# noisy.net
KiCad netlist of a schematic drawn in EAGLE
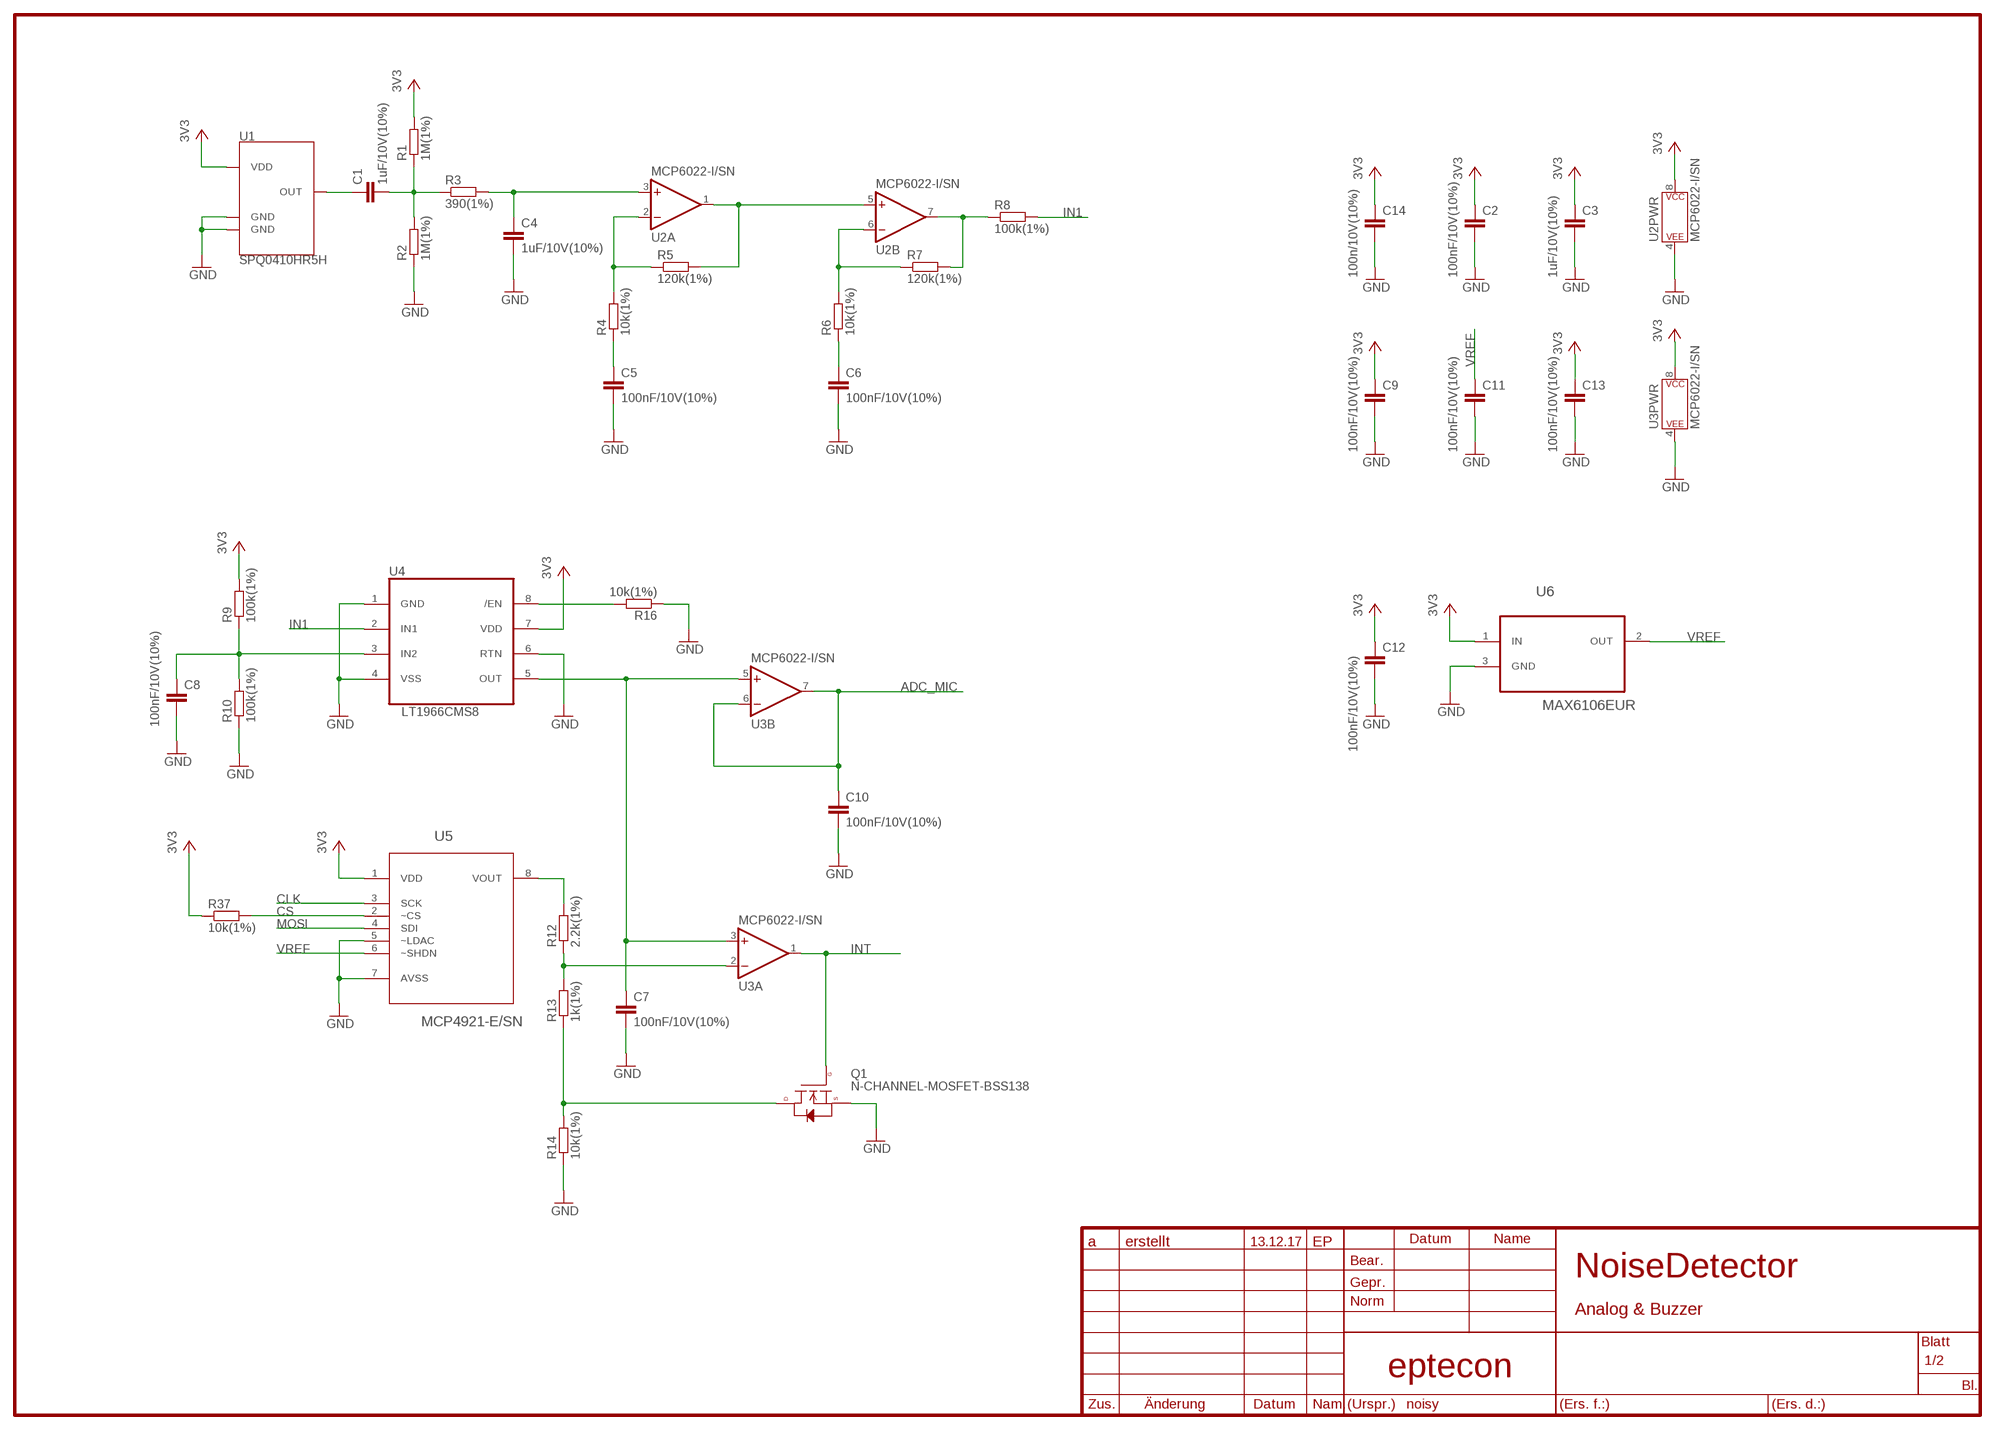
[diagram p0: schematic, sheet 1]
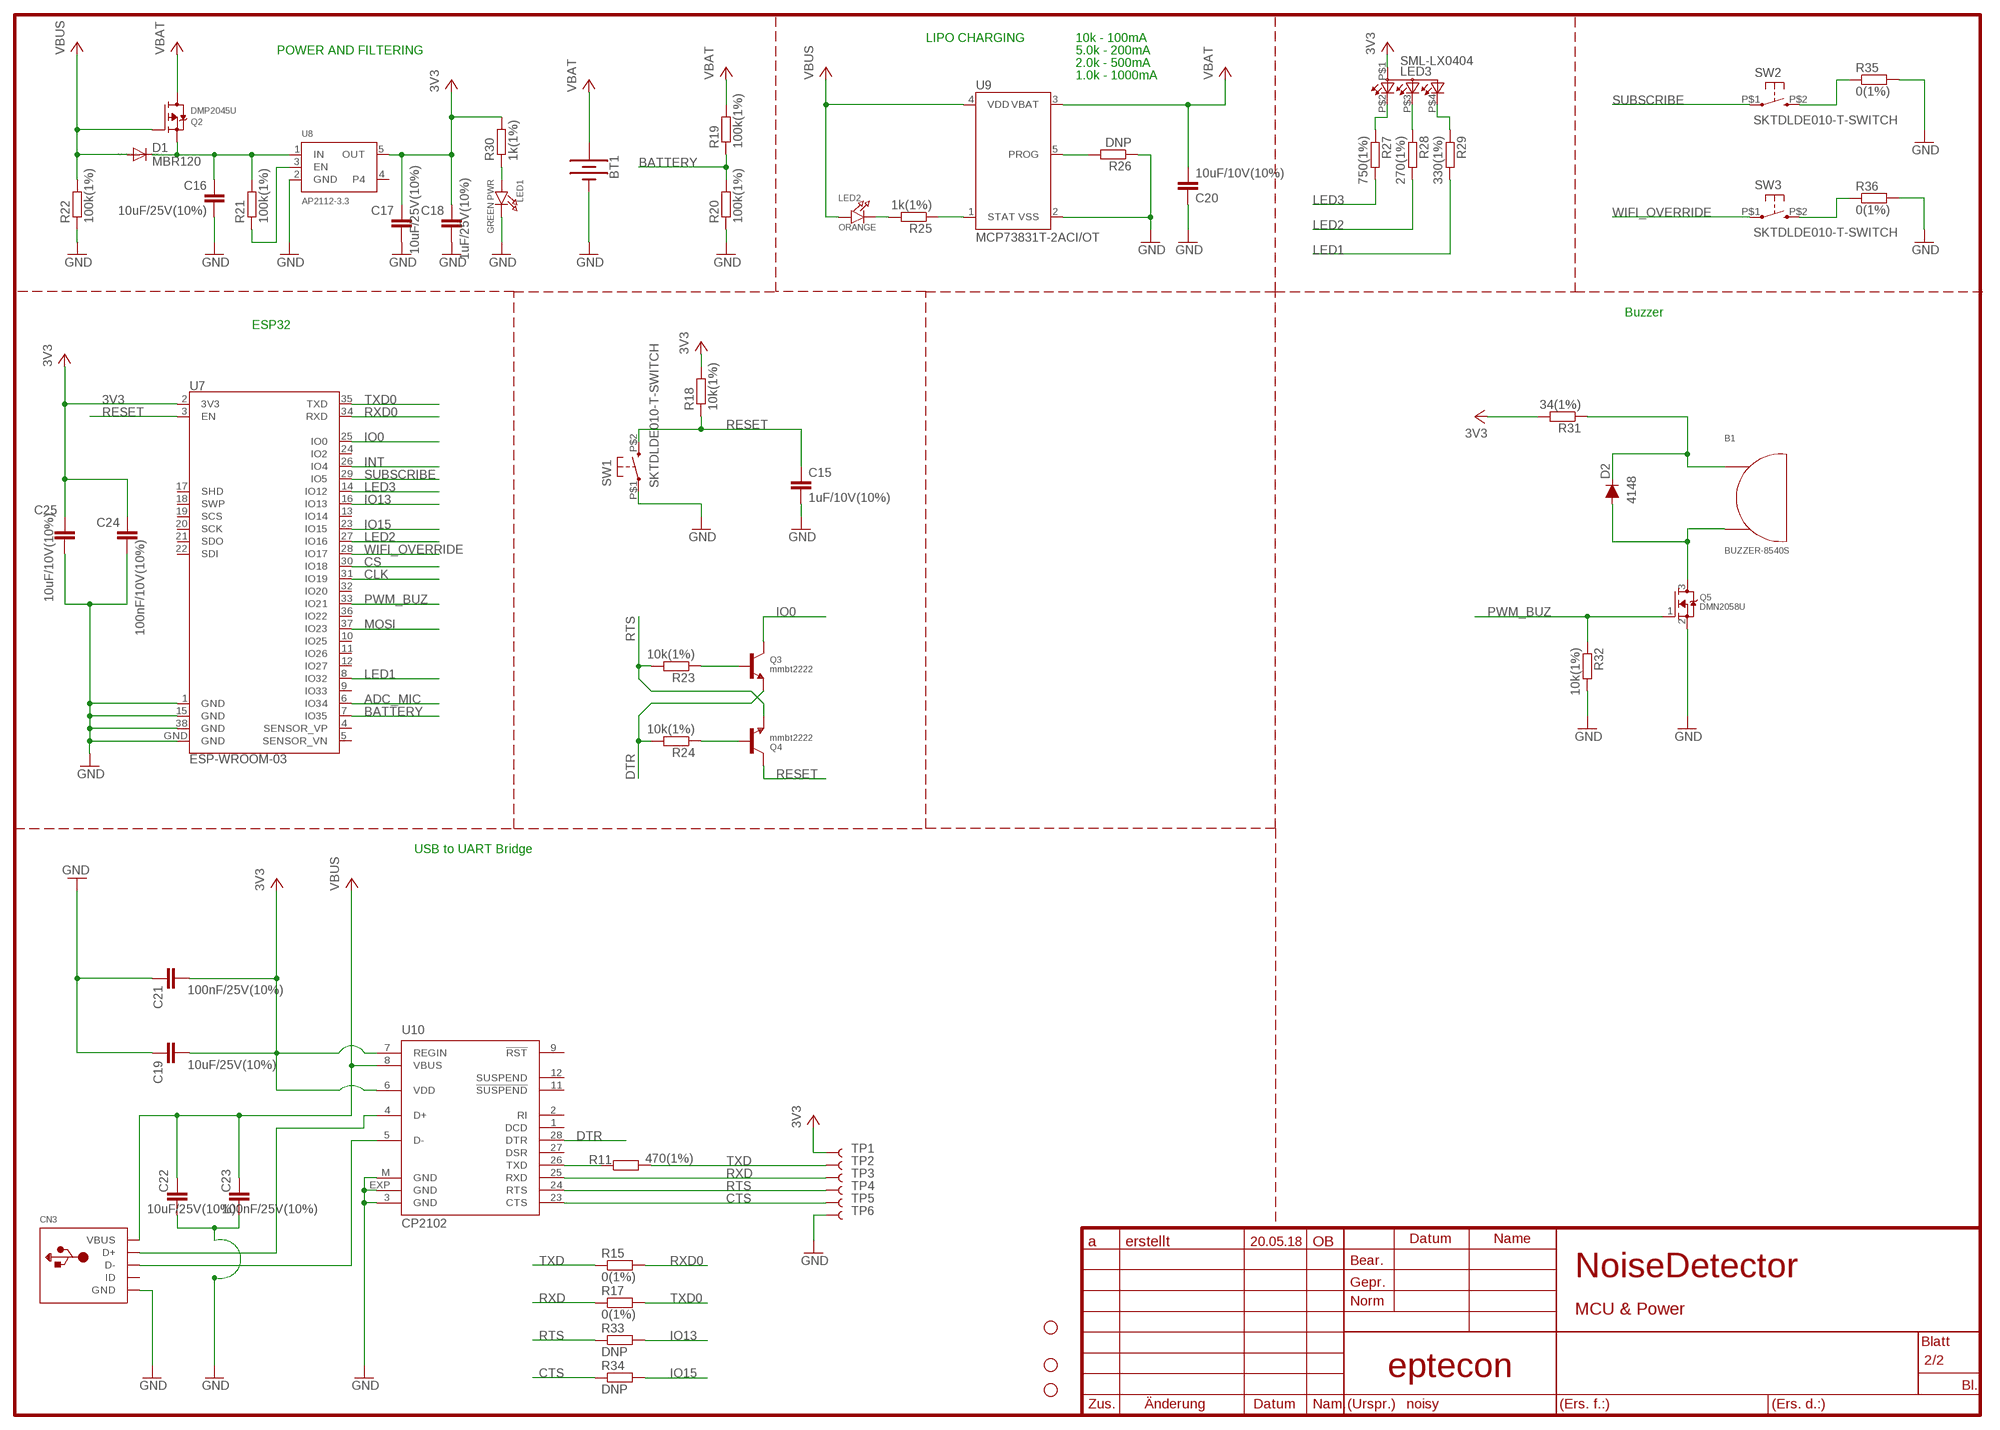
[diagram p1: schematic, sheet 2]

(export (version "E")
  (design (tool "Eeschema 10.0.6"))
  (components
    (comp (ref "B1")
      (value "BUZZER-8540S")
      (footprint "eagle-import:BUZZER-8540S")
      (libsource (lib "eagle-import") (part "BUZZER-8540S"))
    )
    (comp (ref "BT1")
      (value "BATTERY-AA")
      (footprint "eagle-import:BATTERY-AA")
      (libsource (lib "eagle-import") (part "BATTERY-AA"))
    )
    (comp (ref "C15")
      (value "1uF/10V(10%)")
      (footprint "eagle-import:C0603")
      (libsource (lib "eagle-import") (part "C-EUC0603"))
    )
    (comp (ref "C16")
      (value "10uF/25V(10%)")
      (footprint "eagle-import:C0603")
      (libsource (lib "eagle-import") (part "C-EUC0603"))
    )
    (comp (ref "C17")
      (value "10uF/25V(10%)")
      (footprint "eagle-import:C0603")
      (libsource (lib "eagle-import") (part "C-EUC0603"))
    )
    (comp (ref "C18")
      (value "1uF/25V(10%)")
      (footprint "eagle-import:C0603")
      (libsource (lib "eagle-import") (part "C-EUC0603"))
    )
    (comp (ref "C19")
      (value "10uF/25V(10%)")
      (footprint "eagle-import:C0603")
      (libsource (lib "eagle-import") (part "C-EUC0603"))
    )
    (comp (ref "C20")
      (value "10uF/10V(10%)")
      (footprint "eagle-import:C0603")
      (libsource (lib "eagle-import") (part "C-EUC0603"))
    )
    (comp (ref "C21")
      (value "100nF/25V(10%)")
      (footprint "eagle-import:C0603")
      (libsource (lib "eagle-import") (part "C-EUC0603"))
    )
    (comp (ref "C22")
      (value "10uF/25V(10%)")
      (footprint "eagle-import:C0603")
      (libsource (lib "eagle-import") (part "C-EUC0603"))
    )
    (comp (ref "C23")
      (value "100nF/25V(10%)")
      (footprint "eagle-import:C0603")
      (libsource (lib "eagle-import") (part "C-EUC0603"))
    )
    (comp (ref "C24")
      (value "100nF/10V(10%)")
      (footprint "eagle-import:C0603")
      (libsource (lib "eagle-import") (part "C-EUC0603"))
    )
    (comp (ref "C25")
      (value "10uF/10V(10%)")
      (footprint "eagle-import:C0603")
      (libsource (lib "eagle-import") (part "C-EUC0603"))
    )
    (comp (ref "CN3")
      (value "USBMINIBLARGE")
      (footprint "eagle-import:USB-MINIB_LARGER")
      (libsource (lib "eagle-import") (part "USBMINIBLARGE"))
    )
    (comp (ref "D1")
      (value "MBR120")
      (footprint "eagle-import:SOD123")
      (libsource (lib "eagle-import") (part "MBR0520LT"))
    )
    (comp (ref "D2")
      (value "4148")
      (footprint "eagle-import:SOD-323")
      (libsource (lib "eagle-import") (part "DIODE-BAS16J"))
    )
    (comp (ref "H1")
      (value "STAND-OFF")
      (footprint "eagle-import:STAND-OFF")
      (libsource (lib "eagle-import") (part "STAND-OFF"))
    )
    (comp (ref "H2")
      (value "STAND-OFF")
      (footprint "eagle-import:STAND-OFF")
      (libsource (lib "eagle-import") (part "STAND-OFF"))
    )
    (comp (ref "H3")
      (value "STAND-OFF")
      (footprint "eagle-import:STAND-OFF")
      (libsource (lib "eagle-import") (part "STAND-OFF"))
    )
    (comp (ref "LED1")
      (value "GREEN PWR")
      (footprint "eagle-import:CHIPLED_0805_NOOUTLINE")
      (libsource (lib "eagle-import") (part "LED0805_NOOUTLINE"))
    )
    (comp (ref "LED2")
      (value "ORANGE")
      (footprint "eagle-import:CHIPLED_0805_NOOUTLINE")
      (libsource (lib "eagle-import") (part "LED0805_NOOUTLINE"))
    )
    (comp (ref "LED3")
      (value "SML-LX0404")
      (footprint "eagle-import:LED_RGB")
      (libsource (lib "eagle-import") (part "SML-LX0404"))
    )
    (comp (ref "Q2")
      (value "DMP2045U")
      (footprint "eagle-import:SOT23-R")
      (libsource (lib "eagle-import") (part "MOSFET-P"))
    )
    (comp (ref "Q3")
      (value "mmbt2222")
      (footprint "eagle-import:SOT23-R")
      (libsource (lib "eagle-import") (part "TRANSISTOR_NPN"))
    )
    (comp (ref "Q4")
      (value "mmbt2222")
      (footprint "eagle-import:SOT23-R")
      (libsource (lib "eagle-import") (part "TRANSISTOR_NPN"))
    )
    (comp (ref "Q5")
      (value "DMN2058U")
      (footprint "eagle-import:SOT23-R")
      (libsource (lib "eagle-import") (part "MOSFET-NREFLOW"))
    )
    (comp (ref "R11")
      (value "470(1%)")
      (footprint "eagle-import:R0603")
      (libsource (lib "eagle-import") (part "R-EU_R0603"))
    )
    (comp (ref "R15")
      (value "0(1%)")
      (footprint "eagle-import:R0603")
      (libsource (lib "eagle-import") (part "R-EU_R0603"))
    )
    (comp (ref "R17")
      (value "0(1%)")
      (footprint "eagle-import:R0603")
      (libsource (lib "eagle-import") (part "R-EU_R0603"))
    )
    (comp (ref "R18")
      (value "10k(1%)")
      (footprint "eagle-import:R0603")
      (libsource (lib "eagle-import") (part "R-EU_R0603"))
    )
    (comp (ref "R19")
      (value "100k(1%)")
      (footprint "eagle-import:R0603")
      (libsource (lib "eagle-import") (part "R-EU_R0603"))
    )
    (comp (ref "R20")
      (value "100k(1%)")
      (footprint "eagle-import:R0603")
      (libsource (lib "eagle-import") (part "R-EU_R0603"))
    )
    (comp (ref "R21")
      (value "100k(1%)")
      (footprint "eagle-import:R0603")
      (libsource (lib "eagle-import") (part "R-EU_R0603"))
    )
    (comp (ref "R22")
      (value "100k(1%)")
      (footprint "eagle-import:R0603")
      (libsource (lib "eagle-import") (part "R-EU_R0603"))
    )
    (comp (ref "R23")
      (value "10k(1%)")
      (footprint "eagle-import:R0603")
      (libsource (lib "eagle-import") (part "R-EU_R0603"))
    )
    (comp (ref "R24")
      (value "10k(1%)")
      (footprint "eagle-import:R0603")
      (libsource (lib "eagle-import") (part "R-EU_R0603"))
    )
    (comp (ref "R25")
      (value "1k(1%)")
      (footprint "eagle-import:R0603")
      (libsource (lib "eagle-import") (part "R-EU_R0603"))
    )
    (comp (ref "R26")
      (value "DNP")
      (footprint "eagle-import:R0603")
      (libsource (lib "eagle-import") (part "R-EU_R0603"))
    )
    (comp (ref "R27")
      (value "750(1%)")
      (footprint "eagle-import:R0603")
      (libsource (lib "eagle-import") (part "R-EU_R0603"))
    )
    (comp (ref "R28")
      (value "270(1%)")
      (footprint "eagle-import:R0603")
      (libsource (lib "eagle-import") (part "R-EU_R0603"))
    )
    (comp (ref "R29")
      (value "330(1%)")
      (footprint "eagle-import:R0603")
      (libsource (lib "eagle-import") (part "R-EU_R0603"))
    )
    (comp (ref "R30")
      (value "1k(1%)")
      (footprint "eagle-import:R0603")
      (libsource (lib "eagle-import") (part "R-EU_R0603"))
    )
    (comp (ref "R31")
      (value "34(1%)")
      (footprint "eagle-import:R0603")
      (libsource (lib "eagle-import") (part "R-EU_R0603"))
    )
    (comp (ref "R32")
      (value "10k(1%)")
      (footprint "eagle-import:R0603")
      (libsource (lib "eagle-import") (part "R-EU_R0603"))
    )
    (comp (ref "R33")
      (value "DNP")
      (footprint "eagle-import:R0603")
      (libsource (lib "eagle-import") (part "R-EU_R0603"))
    )
    (comp (ref "R34")
      (value "DNP")
      (footprint "eagle-import:R0603")
      (libsource (lib "eagle-import") (part "R-EU_R0603"))
    )
    (comp (ref "R35")
      (value "0(1%)")
      (footprint "eagle-import:R0603")
      (libsource (lib "eagle-import") (part "R-EU_R0603"))
    )
    (comp (ref "R36")
      (value "0(1%)")
      (footprint "eagle-import:R0603")
      (libsource (lib "eagle-import") (part "R-EU_R0603"))
    )
    (comp (ref "SW1")
      (value "SKTDLDE010-T-SWITCH")
      (footprint "eagle-import:T-SWITCH-ALPS-2")
      (libsource (lib "eagle-import") (part "SKTDLDE010-T-SWITCH"))
    )
    (comp (ref "SW2")
      (value "SKTDLDE010-T-SWITCH")
      (footprint "eagle-import:T-SWITCH-ALPS-2")
      (libsource (lib "eagle-import") (part "SKTDLDE010-T-SWITCH"))
    )
    (comp (ref "SW3")
      (value "SKTDLDE010-T-SWITCH")
      (footprint "eagle-import:T-SWITCH-ALPS-2")
      (libsource (lib "eagle-import") (part "SKTDLDE010-T-SWITCH"))
    )
    (comp (ref "TP1")
      (value "TEST-POINT3X5")
      (footprint "eagle-import:PAD.03X.05")
      (libsource (lib "eagle-import") (part "TEST-POINT3X5"))
    )
    (comp (ref "TP2")
      (value "TEST-POINT3X5")
      (footprint "eagle-import:PAD.03X.05")
      (libsource (lib "eagle-import") (part "TEST-POINT3X5"))
    )
    (comp (ref "TP3")
      (value "TEST-POINT3X5")
      (footprint "eagle-import:PAD.03X.05")
      (libsource (lib "eagle-import") (part "TEST-POINT3X5"))
    )
    (comp (ref "TP4")
      (value "TEST-POINT3X5")
      (footprint "eagle-import:PAD.03X.05")
      (libsource (lib "eagle-import") (part "TEST-POINT3X5"))
    )
    (comp (ref "TP5")
      (value "TEST-POINT3X5")
      (footprint "eagle-import:PAD.03X.05")
      (libsource (lib "eagle-import") (part "TEST-POINT3X5"))
    )
    (comp (ref "TP6")
      (value "TEST-POINT3X5")
      (footprint "eagle-import:PAD.03X.05")
      (libsource (lib "eagle-import") (part "TEST-POINT3X5"))
    )
    (comp (ref "U7")
      (value "ESP-WROOM-03")
      (footprint "eagle-import:ESP-WROOM-03")
      (libsource (lib "eagle-import") (part "ESP-WROOM-03"))
    )
    (comp (ref "U8")
      (value "AP2112-3.3")
      (footprint "eagle-import:SOT23-5")
      (libsource (lib "eagle-import") (part "VREG_SOT23-5"))
    )
    (comp (ref "U9")
      (value "MCP73831T-2ACI/OT")
      (footprint "eagle-import:SOT23-5")
      (libsource (lib "eagle-import") (part "MCP73831"))
    )
    (comp (ref "U10")
      (value "CP2102")
      (footprint "eagle-import:MLP28")
      (fields (field (name "MF") "FARNELL") (field (name "MPN") "CP2102-GM"))
      (libsource (lib "eagle-import") (part "CP2102"))
    )
    (comp (ref "C1")
      (value "1uF/10V(10%)")
      (footprint "eagle-import:C0603")
      (libsource (lib "eagle-import") (part "C-EUC0603"))
    )
    (comp (ref "C2")
      (value "100nF/10V(10%)")
      (footprint "eagle-import:C0603")
      (libsource (lib "eagle-import") (part "C-EUC0603"))
    )
    (comp (ref "C3")
      (value "1uF/10V(10%)")
      (footprint "eagle-import:C0603")
      (libsource (lib "eagle-import") (part "C-EUC0603"))
    )
    (comp (ref "C4")
      (value "1uF/10V(10%)")
      (footprint "eagle-import:C0603")
      (libsource (lib "eagle-import") (part "C-EUC0603"))
    )
    (comp (ref "C5")
      (value "100nF/10V(10%)")
      (footprint "eagle-import:C0603")
      (libsource (lib "eagle-import") (part "C-EUC0603"))
    )
    (comp (ref "C6")
      (value "100nF/10V(10%)")
      (footprint "eagle-import:C0603")
      (libsource (lib "eagle-import") (part "C-EUC0603"))
    )
    (comp (ref "C7")
      (value "100nF/10V(10%)")
      (footprint "eagle-import:C0603")
      (libsource (lib "eagle-import") (part "C-EUC0603"))
    )
    (comp (ref "C8")
      (value "100nF/10V(10%)")
      (footprint "eagle-import:C0603")
      (libsource (lib "eagle-import") (part "C-EUC0603"))
    )
    (comp (ref "C9")
      (value "100nF/10V(10%)")
      (footprint "eagle-import:C0603")
      (libsource (lib "eagle-import") (part "C-EUC0603"))
    )
    (comp (ref "C10")
      (value "100nF/10V(10%)")
      (footprint "eagle-import:C0603")
      (libsource (lib "eagle-import") (part "C-EUC0603"))
    )
    (comp (ref "C11")
      (value "100nF/10V(10%)")
      (footprint "eagle-import:C0603")
      (libsource (lib "eagle-import") (part "C-EUC0603"))
    )
    (comp (ref "C12")
      (value "100nF/10V(10%)")
      (footprint "eagle-import:C0603")
      (libsource (lib "eagle-import") (part "C-EUC0603"))
    )
    (comp (ref "C13")
      (value "100nF/10V(10%)")
      (footprint "eagle-import:C0603")
      (libsource (lib "eagle-import") (part "C-EUC0603"))
    )
    (comp (ref "C14")
      (value "100n/10V(10%)")
      (footprint "eagle-import:C0603")
      (libsource (lib "eagle-import") (part "C-EUC0603"))
    )
    (comp (ref "Q1")
      (value "N-CHANNEL-MOSFET-BSS138")
      (footprint "eagle-import:SOT23-3")
      (libsource (lib "eagle-import") (part "N-CHANNEL-MOSFET-BSS138"))
    )
    (comp (ref "R1")
      (value "1M(1%)")
      (footprint "eagle-import:R0603")
      (libsource (lib "eagle-import") (part "R-EU_R0603"))
    )
    (comp (ref "R2")
      (value "1M(1%)")
      (footprint "eagle-import:R0603")
      (libsource (lib "eagle-import") (part "R-EU_R0603"))
    )
    (comp (ref "R3")
      (value "390(1%)")
      (footprint "eagle-import:R0603")
      (libsource (lib "eagle-import") (part "R-EU_R0603"))
    )
    (comp (ref "R4")
      (value "10k(1%)")
      (footprint "eagle-import:R0603")
      (libsource (lib "eagle-import") (part "R-EU_R0603"))
    )
    (comp (ref "R5")
      (value "120k(1%)")
      (footprint "eagle-import:R0603")
      (libsource (lib "eagle-import") (part "R-EU_R0603"))
    )
    (comp (ref "R6")
      (value "10k(1%)")
      (footprint "eagle-import:R0603")
      (libsource (lib "eagle-import") (part "R-EU_R0603"))
    )
    (comp (ref "R7")
      (value "120k(1%)")
      (footprint "eagle-import:R0603")
      (libsource (lib "eagle-import") (part "R-EU_R0603"))
    )
    (comp (ref "R8")
      (value "100k(1%)")
      (footprint "eagle-import:R0603")
      (libsource (lib "eagle-import") (part "R-EU_R0603"))
    )
    (comp (ref "R9")
      (value "100k(1%)")
      (footprint "eagle-import:R0603")
      (libsource (lib "eagle-import") (part "R-EU_R0603"))
    )
    (comp (ref "R10")
      (value "100k(1%)")
      (footprint "eagle-import:R0603")
      (libsource (lib "eagle-import") (part "R-EU_R0603"))
    )
    (comp (ref "R12")
      (value "2.2k(1%)")
      (footprint "eagle-import:R0603")
      (libsource (lib "eagle-import") (part "R-EU_R0603"))
    )
    (comp (ref "R13")
      (value "1k(1%)")
      (footprint "eagle-import:R0603")
      (libsource (lib "eagle-import") (part "R-EU_R0603"))
    )
    (comp (ref "R14")
      (value "10k(1%)")
      (footprint "eagle-import:R0603")
      (libsource (lib "eagle-import") (part "R-EU_R0603"))
    )
    (comp (ref "R16")
      (value "10k(1%)")
      (footprint "eagle-import:R0603")
      (libsource (lib "eagle-import") (part "R-EU_R0603"))
    )
    (comp (ref "R37")
      (value "10k(1%)")
      (footprint "eagle-import:R0603")
      (libsource (lib "eagle-import") (part "R-EU_R0603"))
    )
    (comp (ref "U1")
      (value "SPQ0410HR5H")
      (footprint "eagle-import:SPQ0410HR")
      (libsource (lib "eagle-import") (part "SPQ0410HR5H"))
    )
    (comp (ref "U2")
      (value "MCP6022-I/SN")
      (footprint "eagle-import:SOIC08")
      (libsource (lib "eagle-import") (part "MCP6022-I/SN"))
    )
    (comp (ref "U3")
      (value "MCP6022-I/SN")
      (footprint "eagle-import:SOIC08")
      (libsource (lib "eagle-import") (part "MCP6022-I/SN"))
    )
    (comp (ref "U4")
      (value "LT1966CMS8")
      (footprint "eagle-import:MSOP8")
      (libsource (lib "eagle-import") (part "LT1966CMS8"))
    )
    (comp (ref "U5")
      (value "MCP4921-E/SN")
      (footprint "eagle-import:SOIC8-N_MC")
      (libsource (lib "eagle-import") (part "MCP4921-E/SN"))
    )
    (comp (ref "U6")
      (value "MAX6106EUR")
      (footprint "eagle-import:SOT23-3")
      (libsource (lib "eagle-import") (part "MAX6106EUR"))
    )
  )
  (nets
    (net (code "1") (name "3V3") (class "Default")
      (node (ref "C12") (pin "1") (pinfunction "1_1") (pintype "passive"))
      (node (ref "C13") (pin "1") (pinfunction "1_1") (pintype "passive"))
      (node (ref "C14") (pin "1") (pinfunction "1_1") (pintype "passive"))
      (node (ref "C17") (pin "1") (pinfunction "1_1") (pintype "passive"))
      (node (ref "C18") (pin "1") (pinfunction "1_1") (pintype "passive"))
      (node (ref "C19") (pin "2") (pinfunction "2_2") (pintype "passive"))
      (node (ref "C2") (pin "1") (pinfunction "1_1") (pintype "passive"))
      (node (ref "C21") (pin "2") (pinfunction "2_2") (pintype "passive"))
      (node (ref "C24") (pin "1") (pinfunction "1_1") (pintype "passive"))
      (node (ref "C25") (pin "1") (pinfunction "1_1") (pintype "passive"))
      (node (ref "C3") (pin "1") (pinfunction "1_1") (pintype "passive"))
      (node (ref "C9") (pin "1") (pinfunction "1_1") (pintype "passive"))
      (node (ref "LED3") (pin "P$1") (pinfunction "A2_P$1") (pintype "passive"))
      (node (ref "R1") (pin "2") (pinfunction "2_2") (pintype "passive"))
      (node (ref "R18") (pin "2") (pinfunction "2_2") (pintype "passive"))
      (node (ref "R30") (pin "2") (pinfunction "2_2") (pintype "passive"))
      (node (ref "R31") (pin "2") (pinfunction "2_2") (pintype "passive"))
      (node (ref "R37") (pin "1") (pinfunction "1_1") (pintype "passive"))
      (node (ref "R9") (pin "2") (pinfunction "2_2") (pintype "passive"))
      (node (ref "TP1") (pin "P$1") (pinfunction "1_P$1") (pintype "bidirectional"))
      (node (ref "U1") (pin "P$1") (pinfunction "VDD_P$1") (pintype "bidirectional"))
      (node (ref "U10") (pin "6") (pinfunction "VDD_6") (pintype "power_in"))
      (node (ref "U10") (pin "7") (pinfunction "REGIN_7") (pintype "passive"))
      (node (ref "U2") (pin "8") (pinfunction "P$V+_8") (pintype "bidirectional"))
      (node (ref "U3") (pin "8") (pinfunction "P$V+_8") (pintype "bidirectional"))
      (node (ref "U4") (pin "7") (pinfunction "VDD_7") (pintype "power_in"))
      (node (ref "U5") (pin "1") (pinfunction "VDD_1") (pintype "power_in"))
      (node (ref "U6") (pin "1") (pinfunction "IN_1") (pintype "input"))
      (node (ref "U7") (pin "2") (pinfunction "3V3_2") (pintype "bidirectional"))
      (node (ref "U8") (pin "5") (pinfunction "OUT_5") (pintype "bidirectional"))
    )
    (net (code "2") (name "ADC_MIC") (class "Default")
      (node (ref "C10") (pin "1") (pinfunction "1_1") (pintype "passive"))
      (node (ref "U3") (pin "6") (pinfunction "-IN_6") (pintype "input"))
      (node (ref "U3") (pin "7") (pinfunction "OUT_7") (pintype "output"))
      (node (ref "U7") (pin "6") (pinfunction "IO34_6") (pintype "bidirectional"))
    )
    (net (code "3") (name "BATTERY") (class "Default")
      (node (ref "R19") (pin "1") (pinfunction "1_1") (pintype "passive"))
      (node (ref "R20") (pin "2") (pinfunction "2_2") (pintype "passive"))
      (node (ref "U7") (pin "7") (pinfunction "IO35_7") (pintype "bidirectional"))
    )
    (net (code "4") (name "CLK") (class "Default")
      (node (ref "U5") (pin "3") (pinfunction "SCK_3") (pintype "input"))
      (node (ref "U7") (pin "31") (pinfunction "IO19_31") (pintype "bidirectional"))
    )
    (net (code "5") (name "CS") (class "Default")
      (node (ref "R37") (pin "2") (pinfunction "2_2") (pintype "passive"))
      (node (ref "U5") (pin "2") (pinfunction "~{CS}_2") (pintype "input"))
      (node (ref "U7") (pin "30") (pinfunction "IO18_30") (pintype "bidirectional"))
    )
    (net (code "6") (name "CTS") (class "Default")
      (node (ref "R34") (pin "1") (pinfunction "1_1") (pintype "passive"))
      (node (ref "TP5") (pin "P$1") (pinfunction "1_P$1") (pintype "bidirectional"))
      (node (ref "U10") (pin "23") (pinfunction "CTS_23") (pintype "input"))
    )
    (net (code "7") (name "DTR") (class "Default")
      (node (ref "Q3") (pin "2") (pinfunction "E_2") (pintype "passive"))
      (node (ref "R24") (pin "2") (pinfunction "2_2") (pintype "passive"))
      (node (ref "U10") (pin "28") (pinfunction "DTR_28") (pintype "output"))
    )
    (net (code "8") (name "GND") (class "Default")
      (node (ref "BT1") (pin "GND@1") (pinfunction "-_GND@1") (pintype "power_in"))
      (node (ref "C10") (pin "2") (pinfunction "2_2") (pintype "passive"))
      (node (ref "C11") (pin "2") (pinfunction "2_2") (pintype "passive"))
      (node (ref "C12") (pin "2") (pinfunction "2_2") (pintype "passive"))
      (node (ref "C13") (pin "2") (pinfunction "2_2") (pintype "passive"))
      (node (ref "C14") (pin "2") (pinfunction "2_2") (pintype "passive"))
      (node (ref "C15") (pin "2") (pinfunction "2_2") (pintype "passive"))
      (node (ref "C16") (pin "2") (pinfunction "2_2") (pintype "passive"))
      (node (ref "C17") (pin "2") (pinfunction "2_2") (pintype "passive"))
      (node (ref "C18") (pin "2") (pinfunction "2_2") (pintype "passive"))
      (node (ref "C19") (pin "1") (pinfunction "1_1") (pintype "passive"))
      (node (ref "C2") (pin "2") (pinfunction "2_2") (pintype "passive"))
      (node (ref "C20") (pin "1") (pinfunction "1_1") (pintype "passive"))
      (node (ref "C21") (pin "1") (pinfunction "1_1") (pintype "passive"))
      (node (ref "C22") (pin "1") (pinfunction "1_1") (pintype "passive"))
      (node (ref "C23") (pin "1") (pinfunction "1_1") (pintype "passive"))
      (node (ref "C24") (pin "2") (pinfunction "2_2") (pintype "passive"))
      (node (ref "C25") (pin "2") (pinfunction "2_2") (pintype "passive"))
      (node (ref "C3") (pin "2") (pinfunction "2_2") (pintype "passive"))
      (node (ref "C4") (pin "2") (pinfunction "2_2") (pintype "passive"))
      (node (ref "C5") (pin "2") (pinfunction "2_2") (pintype "passive"))
      (node (ref "C6") (pin "2") (pinfunction "2_2") (pintype "passive"))
      (node (ref "C7") (pin "2") (pinfunction "2_2") (pintype "passive"))
      (node (ref "C8") (pin "2") (pinfunction "2_2") (pintype "passive"))
      (node (ref "C9") (pin "2") (pinfunction "2_2") (pintype "passive"))
      (node (ref "CN3") (pin "GND") (pinfunction "GND_GND") (pintype "power_in"))
      (node (ref "LED1") (pin "C") (pinfunction "C_C") (pintype "passive"))
      (node (ref "Q1") (pin "2") (pinfunction "S_2") (pintype "passive"))
      (node (ref "Q5") (pin "2") (pinfunction "S_2") (pintype "bidirectional"))
      (node (ref "R10") (pin "1") (pinfunction "1_1") (pintype "passive"))
      (node (ref "R14") (pin "1") (pinfunction "1_1") (pintype "passive"))
      (node (ref "R16") (pin "1") (pinfunction "1_1") (pintype "passive"))
      (node (ref "R2") (pin "1") (pinfunction "1_1") (pintype "passive"))
      (node (ref "R20") (pin "1") (pinfunction "1_1") (pintype "passive"))
      (node (ref "R22") (pin "1") (pinfunction "1_1") (pintype "passive"))
      (node (ref "R26") (pin "1") (pinfunction "1_1") (pintype "passive"))
      (node (ref "R32") (pin "2") (pinfunction "2_2") (pintype "passive"))
      (node (ref "R35") (pin "2") (pinfunction "2_2") (pintype "passive"))
      (node (ref "R36") (pin "2") (pinfunction "2_2") (pintype "passive"))
      (node (ref "SW1") (pin "P$1") (pinfunction "1_P$1") (pintype "passive"))
      (node (ref "TP6") (pin "P$1") (pinfunction "1_P$1") (pintype "bidirectional"))
      (node (ref "U1") (pin "P$2") (pinfunction "GND_P$2") (pintype "bidirectional"))
      (node (ref "U1") (pin "P$3") (pinfunction "GND_P$3") (pintype "bidirectional"))
      (node (ref "U10") (pin "3") (pinfunction "GND_3") (pintype "power_in"))
      (node (ref "U10") (pin "EXP") (pinfunction "GND_EXP") (pintype "power_in"))
      (node (ref "U10") (pin "M") (pinfunction "GND_M") (pintype "power_in"))
      (node (ref "U2") (pin "4") (pinfunction "P$V-_4") (pintype "bidirectional"))
      (node (ref "U3") (pin "4") (pinfunction "P$V-_4") (pintype "bidirectional"))
      (node (ref "U4") (pin "1") (pinfunction "GND_1") (pintype "power_in"))
      (node (ref "U4") (pin "4") (pinfunction "VSS_4") (pintype "power_in"))
      (node (ref "U4") (pin "6") (pinfunction "RTN_6") (pintype "passive"))
      (node (ref "U5") (pin "5") (pinfunction "~{LDAC}_5") (pintype "input"))
      (node (ref "U5") (pin "7") (pinfunction "AVSS_7") (pintype "power_in"))
      (node (ref "U6") (pin "3") (pinfunction "GND_3") (pintype "passive"))
      (node (ref "U7") (pin "1") (pinfunction "GND_1") (pintype "bidirectional"))
      (node (ref "U7") (pin "15") (pinfunction "GND_15") (pintype "bidirectional"))
      (node (ref "U7") (pin "38") (pinfunction "GND_38") (pintype "bidirectional"))
      (node (ref "U7") (pin "GND") (pinfunction "GND_GND") (pintype "bidirectional"))
      (node (ref "U8") (pin "2") (pinfunction "GND_2") (pintype "bidirectional"))
      (node (ref "U9") (pin "2") (pinfunction "VSS_2") (pintype "power_in"))
    )
    (net (code "9") (name "IN1") (class "Default")
      (node (ref "R8") (pin "2") (pinfunction "2_2") (pintype "passive"))
      (node (ref "U4") (pin "2") (pinfunction "IN1_2") (pintype "input"))
    )
    (net (code "10") (name "INT") (class "Default")
      (node (ref "Q1") (pin "1") (pinfunction "G_1") (pintype "passive"))
      (node (ref "U3") (pin "1") (pinfunction "OUT_1") (pintype "output"))
      (node (ref "U7") (pin "26") (pinfunction "IO4_26") (pintype "bidirectional"))
    )
    (net (code "11") (name "IO0") (class "Default")
      (node (ref "Q3") (pin "3") (pinfunction "C_3") (pintype "passive"))
      (node (ref "U7") (pin "25") (pinfunction "IO0_25") (pintype "bidirectional"))
    )
    (net (code "12") (name "IO13") (class "Default")
      (node (ref "R33") (pin "2") (pinfunction "2_2") (pintype "passive"))
      (node (ref "U7") (pin "16") (pinfunction "IO13_16") (pintype "bidirectional"))
    )
    (net (code "13") (name "IO15") (class "Default")
      (node (ref "R34") (pin "2") (pinfunction "2_2") (pintype "passive"))
      (node (ref "U7") (pin "23") (pinfunction "IO15_23") (pintype "bidirectional"))
    )
    (net (code "14") (name "LED1") (class "Default")
      (node (ref "R29") (pin "2") (pinfunction "2_2") (pintype "passive"))
      (node (ref "U7") (pin "8") (pinfunction "IO32_8") (pintype "bidirectional"))
    )
    (net (code "15") (name "LED2") (class "Default")
      (node (ref "R28") (pin "2") (pinfunction "2_2") (pintype "passive"))
      (node (ref "U7") (pin "27") (pinfunction "IO16_27") (pintype "bidirectional"))
    )
    (net (code "16") (name "LED3") (class "Default")
      (node (ref "R27") (pin "2") (pinfunction "2_2") (pintype "passive"))
      (node (ref "U7") (pin "14") (pinfunction "IO12_14") (pintype "bidirectional"))
    )
    (net (code "17") (name "MOSI") (class "Default")
      (node (ref "U5") (pin "4") (pinfunction "SDI_4") (pintype "input"))
      (node (ref "U7") (pin "37") (pinfunction "IO23_37") (pintype "bidirectional"))
    )
    (net (code "18") (name "Net-(B1-PadPLUS)") (class "Default")
      (node (ref "B1") (pin "PLUS") (pinfunction "PLUS_PLUS") (pintype "bidirectional"))
      (node (ref "D2") (pin "C") (pinfunction "C_C") (pintype "passive"))
      (node (ref "R31") (pin "1") (pinfunction "1_1") (pintype "passive"))
    )
    (net (code "19") (name "Net-(C1-Pad2)") (class "Default")
      (node (ref "C1") (pin "2") (pinfunction "2_2") (pintype "passive"))
      (node (ref "R1") (pin "1") (pinfunction "1_1") (pintype "passive"))
      (node (ref "R2") (pin "2") (pinfunction "2_2") (pintype "passive"))
      (node (ref "R3") (pin "1") (pinfunction "1_1") (pintype "passive"))
    )
    (net (code "20") (name "Net-(C5-Pad1)") (class "Default")
      (node (ref "C5") (pin "1") (pinfunction "1_1") (pintype "passive"))
      (node (ref "R4") (pin "1") (pinfunction "1_1") (pintype "passive"))
    )
    (net (code "21") (name "Net-(C6-Pad1)") (class "Default")
      (node (ref "C6") (pin "1") (pinfunction "1_1") (pintype "passive"))
      (node (ref "R6") (pin "1") (pinfunction "1_1") (pintype "passive"))
    )
    (net (code "22") (name "Net-(LED1-PadA)") (class "Default")
      (node (ref "LED1") (pin "A") (pinfunction "A_A") (pintype "passive"))
      (node (ref "R30") (pin "1") (pinfunction "1_1") (pintype "passive"))
    )
    (net (code "23") (name "Net-(LED2-PadC)") (class "Default")
      (node (ref "LED2") (pin "C") (pinfunction "C_C") (pintype "passive"))
      (node (ref "R25") (pin "2") (pinfunction "2_2") (pintype "passive"))
    )
    (net (code "24") (name "Net-(LED3-CBLUE)") (class "Default")
      (node (ref "LED3") (pin "P$3") (pinfunction "CBLUE_P$3") (pintype "passive"))
      (node (ref "R28") (pin "1") (pinfunction "1_1") (pintype "passive"))
    )
    (net (code "25") (name "Net-(LED3-CGREEN)") (class "Default")
      (node (ref "LED3") (pin "P$4") (pinfunction "CGREEN_P$4") (pintype "passive"))
      (node (ref "R29") (pin "1") (pinfunction "1_1") (pintype "passive"))
    )
    (net (code "26") (name "Net-(LED3-CRED)") (class "Default")
      (node (ref "LED3") (pin "P$2") (pinfunction "CRED_P$2") (pintype "passive"))
      (node (ref "R27") (pin "1") (pinfunction "1_1") (pintype "passive"))
    )
    (net (code "27") (name "Net-(Q1-D)") (class "Default")
      (node (ref "Q1") (pin "3") (pinfunction "D_3") (pintype "passive"))
      (node (ref "R13") (pin "1") (pinfunction "1_1") (pintype "passive"))
      (node (ref "R14") (pin "2") (pinfunction "2_2") (pintype "passive"))
    )
    (net (code "28") (name "Net-(Q2-S)") (class "Default")
      (node (ref "C16") (pin "1") (pinfunction "1_1") (pintype "passive"))
      (node (ref "D1") (pin "C") (pinfunction "C_C") (pintype "passive"))
      (node (ref "Q2") (pin "2") (pinfunction "S_2") (pintype "passive"))
      (node (ref "R21") (pin "2") (pinfunction "2_2") (pintype "passive"))
      (node (ref "U8") (pin "1") (pinfunction "IN_1") (pintype "bidirectional"))
    )
    (net (code "29") (name "Net-(Q3-B)") (class "Default")
      (node (ref "Q3") (pin "1") (pinfunction "B_1") (pintype "passive"))
      (node (ref "R23") (pin "1") (pinfunction "1_1") (pintype "passive"))
    )
    (net (code "30") (name "Net-(Q4-B)") (class "Default")
      (node (ref "Q4") (pin "1") (pinfunction "B_1") (pintype "passive"))
      (node (ref "R24") (pin "1") (pinfunction "1_1") (pintype "passive"))
    )
    (net (code "31") (name "Net-(Q5-D)") (class "Default")
      (node (ref "B1") (pin "MINUS") (pinfunction "MINUS_MINUS") (pintype "bidirectional"))
      (node (ref "D2") (pin "A") (pinfunction "A_A") (pintype "passive"))
      (node (ref "Q5") (pin "3") (pinfunction "D_3") (pintype "bidirectional"))
    )
    (net (code "32") (name "Net-(SW2-3)") (class "Default")
      (node (ref "R35") (pin "1") (pinfunction "1_1") (pintype "passive"))
      (node (ref "SW2") (pin "P$2") (pinfunction "3_P$2") (pintype "passive"))
    )
    (net (code "33") (name "Net-(SW3-3)") (class "Default")
      (node (ref "R36") (pin "1") (pinfunction "1_1") (pintype "passive"))
      (node (ref "SW3") (pin "P$2") (pinfunction "3_P$2") (pintype "passive"))
    )
    (net (code "34") (name "Net-(U1-OUT)") (class "Default")
      (node (ref "C1") (pin "1") (pinfunction "1_1") (pintype "passive"))
      (node (ref "U1") (pin "P$4") (pinfunction "OUT_P$4") (pintype "bidirectional"))
    )
    (net (code "35") (name "Net-(U2A-+IN)") (class "Default")
      (node (ref "C4") (pin "1") (pinfunction "1_1") (pintype "passive"))
      (node (ref "R3") (pin "2") (pinfunction "2_2") (pintype "passive"))
      (node (ref "U2") (pin "3") (pinfunction "+IN_3") (pintype "input"))
    )
    (net (code "36") (name "Net-(U2A--IN)") (class "Default")
      (node (ref "R4") (pin "2") (pinfunction "2_2") (pintype "passive"))
      (node (ref "R5") (pin "1") (pinfunction "1_1") (pintype "passive"))
      (node (ref "U2") (pin "2") (pinfunction "-IN_2") (pintype "input"))
    )
    (net (code "37") (name "Net-(U2A-OUT)") (class "Default")
      (node (ref "R5") (pin "2") (pinfunction "2_2") (pintype "passive"))
      (node (ref "U2") (pin "1") (pinfunction "OUT_1") (pintype "output"))
      (node (ref "U2") (pin "5") (pinfunction "+IN_5") (pintype "input"))
    )
    (net (code "38") (name "Net-(U2B--IN)") (class "Default")
      (node (ref "R6") (pin "2") (pinfunction "2_2") (pintype "passive"))
      (node (ref "R7") (pin "1") (pinfunction "1_1") (pintype "passive"))
      (node (ref "U2") (pin "6") (pinfunction "-IN_6") (pintype "input"))
    )
    (net (code "39") (name "Net-(U2B-OUT)") (class "Default")
      (node (ref "R7") (pin "2") (pinfunction "2_2") (pintype "passive"))
      (node (ref "R8") (pin "1") (pinfunction "1_1") (pintype "passive"))
      (node (ref "U2") (pin "7") (pinfunction "OUT_7") (pintype "output"))
    )
    (net (code "40") (name "Net-(U3A-+IN)") (class "Default")
      (node (ref "C7") (pin "1") (pinfunction "1_1") (pintype "passive"))
      (node (ref "U3") (pin "3") (pinfunction "+IN_3") (pintype "input"))
      (node (ref "U3") (pin "5") (pinfunction "+IN_5") (pintype "input"))
      (node (ref "U4") (pin "5") (pinfunction "OUT_5") (pintype "output"))
    )
    (net (code "41") (name "Net-(U3A--IN)") (class "Default")
      (node (ref "R12") (pin "1") (pinfunction "1_1") (pintype "passive"))
      (node (ref "R13") (pin "2") (pinfunction "2_2") (pintype "passive"))
      (node (ref "U3") (pin "2") (pinfunction "-IN_2") (pintype "input"))
    )
    (net (code "42") (name "Net-(U4-IN2)") (class "Default")
      (node (ref "C8") (pin "1") (pinfunction "1_1") (pintype "passive"))
      (node (ref "R10") (pin "2") (pinfunction "2_2") (pintype "passive"))
      (node (ref "R9") (pin "1") (pinfunction "1_1") (pintype "passive"))
      (node (ref "U4") (pin "3") (pinfunction "IN2_3") (pintype "input"))
    )
    (net (code "43") (name "Net-(U4-{slash}EN)") (class "Default")
      (node (ref "R16") (pin "2") (pinfunction "2_2") (pintype "passive"))
      (node (ref "U4") (pin "8") (pinfunction "/EN_8") (pintype "input"))
    )
    (net (code "44") (name "Net-(U5-VOUT)") (class "Default")
      (node (ref "R12") (pin "2") (pinfunction "2_2") (pintype "passive"))
      (node (ref "U5") (pin "8") (pinfunction "VOUT_8") (pintype "output"))
    )
    (net (code "45") (name "Net-(U8-EN)") (class "Default")
      (node (ref "R21") (pin "1") (pinfunction "1_1") (pintype "passive"))
      (node (ref "U8") (pin "3") (pinfunction "EN_3") (pintype "bidirectional"))
    )
    (net (code "46") (name "Net-(U9-PROG)") (class "Default")
      (node (ref "R26") (pin "2") (pinfunction "2_2") (pintype "passive"))
      (node (ref "U9") (pin "5") (pinfunction "PROG_5") (pintype "input"))
    )
    (net (code "47") (name "Net-(U9-STAT)") (class "Default")
      (node (ref "R25") (pin "1") (pinfunction "1_1") (pintype "passive"))
      (node (ref "U9") (pin "1") (pinfunction "STAT_1") (pintype "output"))
    )
    (net (code "48") (name "Net-(U10-D+)") (class "Default")
      (node (ref "CN3") (pin "D+") (pinfunction "D+_D+") (pintype "bidirectional"))
      (node (ref "U10") (pin "4") (pinfunction "D+_4") (pintype "bidirectional"))
    )
    (net (code "49") (name "Net-(U10-D-)") (class "Default")
      (node (ref "CN3") (pin "D-") (pinfunction "D-_D-") (pintype "bidirectional"))
      (node (ref "U10") (pin "5") (pinfunction "D-_5") (pintype "bidirectional"))
    )
    (net (code "50") (name "Net-(U10-TXD)") (class "Default")
      (node (ref "R11") (pin "1") (pinfunction "1_1") (pintype "passive"))
      (node (ref "U10") (pin "26") (pinfunction "TXD_26") (pintype "output"))
    )
    (net (code "51") (name "PWM_BUZ") (class "Default")
      (node (ref "Q5") (pin "1") (pinfunction "G_1") (pintype "bidirectional"))
      (node (ref "R32") (pin "1") (pinfunction "1_1") (pintype "passive"))
      (node (ref "U7") (pin "33") (pinfunction "IO21_33") (pintype "bidirectional"))
    )
    (net (code "52") (name "RESET") (class "Default")
      (node (ref "C15") (pin "1") (pinfunction "1_1") (pintype "passive"))
      (node (ref "Q4") (pin "3") (pinfunction "C_3") (pintype "passive"))
      (node (ref "R18") (pin "1") (pinfunction "1_1") (pintype "passive"))
      (node (ref "SW1") (pin "P$2") (pinfunction "3_P$2") (pintype "passive"))
      (node (ref "U7") (pin "3") (pinfunction "EN_3") (pintype "bidirectional"))
    )
    (net (code "53") (name "RTS") (class "Default")
      (node (ref "Q4") (pin "2") (pinfunction "E_2") (pintype "passive"))
      (node (ref "R23") (pin "2") (pinfunction "2_2") (pintype "passive"))
      (node (ref "R33") (pin "1") (pinfunction "1_1") (pintype "passive"))
      (node (ref "TP4") (pin "P$1") (pinfunction "1_P$1") (pintype "bidirectional"))
      (node (ref "U10") (pin "24") (pinfunction "RTS_24") (pintype "output"))
    )
    (net (code "54") (name "RXD") (class "Default")
      (node (ref "R17") (pin "1") (pinfunction "1_1") (pintype "passive"))
      (node (ref "TP3") (pin "P$1") (pinfunction "1_P$1") (pintype "bidirectional"))
      (node (ref "U10") (pin "25") (pinfunction "RXD_25") (pintype "input"))
    )
    (net (code "55") (name "RXD0") (class "Default")
      (node (ref "R15") (pin "2") (pinfunction "2_2") (pintype "passive"))
      (node (ref "U7") (pin "34") (pinfunction "RXD_34") (pintype "bidirectional"))
    )
    (net (code "56") (name "SUBSCRIBE") (class "Default")
      (node (ref "SW2") (pin "P$1") (pinfunction "1_P$1") (pintype "passive"))
      (node (ref "U7") (pin "29") (pinfunction "IO5_29") (pintype "bidirectional"))
    )
    (net (code "57") (name "TXD") (class "Default")
      (node (ref "R11") (pin "2") (pinfunction "2_2") (pintype "passive"))
      (node (ref "R15") (pin "1") (pinfunction "1_1") (pintype "passive"))
      (node (ref "TP2") (pin "P$1") (pinfunction "1_P$1") (pintype "bidirectional"))
    )
    (net (code "58") (name "TXD0") (class "Default")
      (node (ref "R17") (pin "2") (pinfunction "2_2") (pintype "passive"))
      (node (ref "U7") (pin "35") (pinfunction "TXD_35") (pintype "bidirectional"))
    )
    (net (code "59") (name "VBAT") (class "Default")
      (node (ref "BT1") (pin "PWR@1") (pinfunction "+_PWR@1") (pintype "power_in"))
      (node (ref "C20") (pin "2") (pinfunction "2_2") (pintype "passive"))
      (node (ref "Q2") (pin "3") (pinfunction "D_3") (pintype "passive"))
      (node (ref "R19") (pin "2") (pinfunction "2_2") (pintype "passive"))
      (node (ref "U9") (pin "3") (pinfunction "VBAT_3") (pintype "power_in"))
    )
    (net (code "60") (name "VBUS") (class "Default")
      (node (ref "C22") (pin "2") (pinfunction "2_2") (pintype "passive"))
      (node (ref "C23") (pin "2") (pinfunction "2_2") (pintype "passive"))
      (node (ref "CN3") (pin "VBUS") (pinfunction "VBUS_VBUS") (pintype "power_in"))
      (node (ref "D1") (pin "A") (pinfunction "A_A") (pintype "passive"))
      (node (ref "LED2") (pin "A") (pinfunction "A_A") (pintype "passive"))
      (node (ref "Q2") (pin "1") (pinfunction "G_1") (pintype "passive"))
      (node (ref "R22") (pin "2") (pinfunction "2_2") (pintype "passive"))
      (node (ref "U10") (pin "8") (pinfunction "VBUS_8") (pintype "input"))
      (node (ref "U9") (pin "4") (pinfunction "VDD_4") (pintype "power_in"))
    )
    (net (code "61") (name "VREF") (class "Default")
      (node (ref "C11") (pin "1") (pinfunction "1_1") (pintype "passive"))
      (node (ref "U5") (pin "6") (pinfunction "~{SHDN}_6") (pintype "input"))
      (node (ref "U6") (pin "2") (pinfunction "OUT_2") (pintype "output"))
    )
    (net (code "62") (name "WIFI_OVERRIDE") (class "Default")
      (node (ref "SW3") (pin "P$1") (pinfunction "1_P$1") (pintype "passive"))
      (node (ref "U7") (pin "28") (pinfunction "IO17_28") (pintype "bidirectional"))
    )
    (net (code "63") (name "unconnected-(CN3-PadID)") (class "Default")
      (node (ref "CN3") (pin "ID") (pinfunction "ID_ID") (pintype "bidirectional"))
    )
    (net (code "64") (name "unconnected-(U7-IO2-Pad24)") (class "Default")
      (node (ref "U7") (pin "24") (pinfunction "IO2_24") (pintype "bidirectional"))
    )
    (net (code "65") (name "unconnected-(U7-IO14-Pad13)") (class "Default")
      (node (ref "U7") (pin "13") (pinfunction "IO14_13") (pintype "bidirectional"))
    )
    (net (code "66") (name "unconnected-(U7-IO20-Pad32)") (class "Default")
      (node (ref "U7") (pin "32") (pinfunction "IO20_32") (pintype "bidirectional"))
    )
    (net (code "67") (name "unconnected-(U7-IO22-Pad36)") (class "Default")
      (node (ref "U7") (pin "36") (pinfunction "IO22_36") (pintype "bidirectional"))
    )
    (net (code "68") (name "unconnected-(U7-IO25-Pad10)") (class "Default")
      (node (ref "U7") (pin "10") (pinfunction "IO25_10") (pintype "bidirectional"))
    )
    (net (code "69") (name "unconnected-(U7-IO26-Pad11)") (class "Default")
      (node (ref "U7") (pin "11") (pinfunction "IO26_11") (pintype "bidirectional"))
    )
    (net (code "70") (name "unconnected-(U7-IO27-Pad12)") (class "Default")
      (node (ref "U7") (pin "12") (pinfunction "IO27_12") (pintype "bidirectional"))
    )
    (net (code "71") (name "unconnected-(U7-IO33-Pad9)") (class "Default")
      (node (ref "U7") (pin "9") (pinfunction "IO33_9") (pintype "bidirectional"))
    )
    (net (code "72") (name "unconnected-(U7-SCK-Pad20)") (class "Default")
      (node (ref "U7") (pin "20") (pinfunction "SCK_20") (pintype "bidirectional"))
    )
    (net (code "73") (name "unconnected-(U7-SCS-Pad19)") (class "Default")
      (node (ref "U7") (pin "19") (pinfunction "SCS_19") (pintype "bidirectional"))
    )
    (net (code "74") (name "unconnected-(U7-SDI-Pad22)") (class "Default")
      (node (ref "U7") (pin "22") (pinfunction "SDI_22") (pintype "bidirectional"))
    )
    (net (code "75") (name "unconnected-(U7-SDO-Pad21)") (class "Default")
      (node (ref "U7") (pin "21") (pinfunction "SDO_21") (pintype "bidirectional"))
    )
    (net (code "76") (name "unconnected-(U7-SENSOR_VN-Pad5)") (class "Default")
      (node (ref "U7") (pin "5") (pinfunction "SENSOR_VN_5") (pintype "bidirectional"))
    )
    (net (code "77") (name "unconnected-(U7-SENSOR_VP-Pad4)") (class "Default")
      (node (ref "U7") (pin "4") (pinfunction "SENSOR_VP_4") (pintype "bidirectional"))
    )
    (net (code "78") (name "unconnected-(U7-SHD-Pad17)") (class "Default")
      (node (ref "U7") (pin "17") (pinfunction "SHD_17") (pintype "bidirectional"))
    )
    (net (code "79") (name "unconnected-(U7-SWP-Pad18)") (class "Default")
      (node (ref "U7") (pin "18") (pinfunction "SWP_18") (pintype "bidirectional"))
    )
    (net (code "80") (name "unconnected-(U8-P4-Pad4)") (class "Default")
      (node (ref "U8") (pin "4") (pinfunction "P4_4") (pintype "bidirectional"))
    )
    (net (code "81") (name "unconnected-(U10-DCD-Pad1)") (class "Default")
      (node (ref "U10") (pin "1") (pinfunction "DCD_1") (pintype "input"))
    )
    (net (code "82") (name "unconnected-(U10-DSR-Pad27)") (class "Default")
      (node (ref "U10") (pin "27") (pinfunction "DSR_27") (pintype "input"))
    )
    (net (code "83") (name "unconnected-(U10-RI-Pad2)") (class "Default")
      (node (ref "U10") (pin "2") (pinfunction "RI_2") (pintype "input"))
    )
    (net (code "84") (name "unconnected-(U10-SUSPEND-Pad12)") (class "Default")
      (node (ref "U10") (pin "12") (pinfunction "SUSPEND_12") (pintype "output"))
    )
    (net (code "85") (name "unconnected-(U10-~{RST}-Pad9)") (class "Default")
      (node (ref "U10") (pin "9") (pinfunction "~{RST}_9") (pintype "bidirectional"))
    )
    (net (code "86") (name "unconnected-(U10-~{SUSPEND}-Pad11)") (class "Default")
      (node (ref "U10") (pin "11") (pinfunction "~{SUSPEND}_11") (pintype "output"))
    )
  )
)
